# p128fet.net
KiCad netlist of a schematic drawn in EAGLE
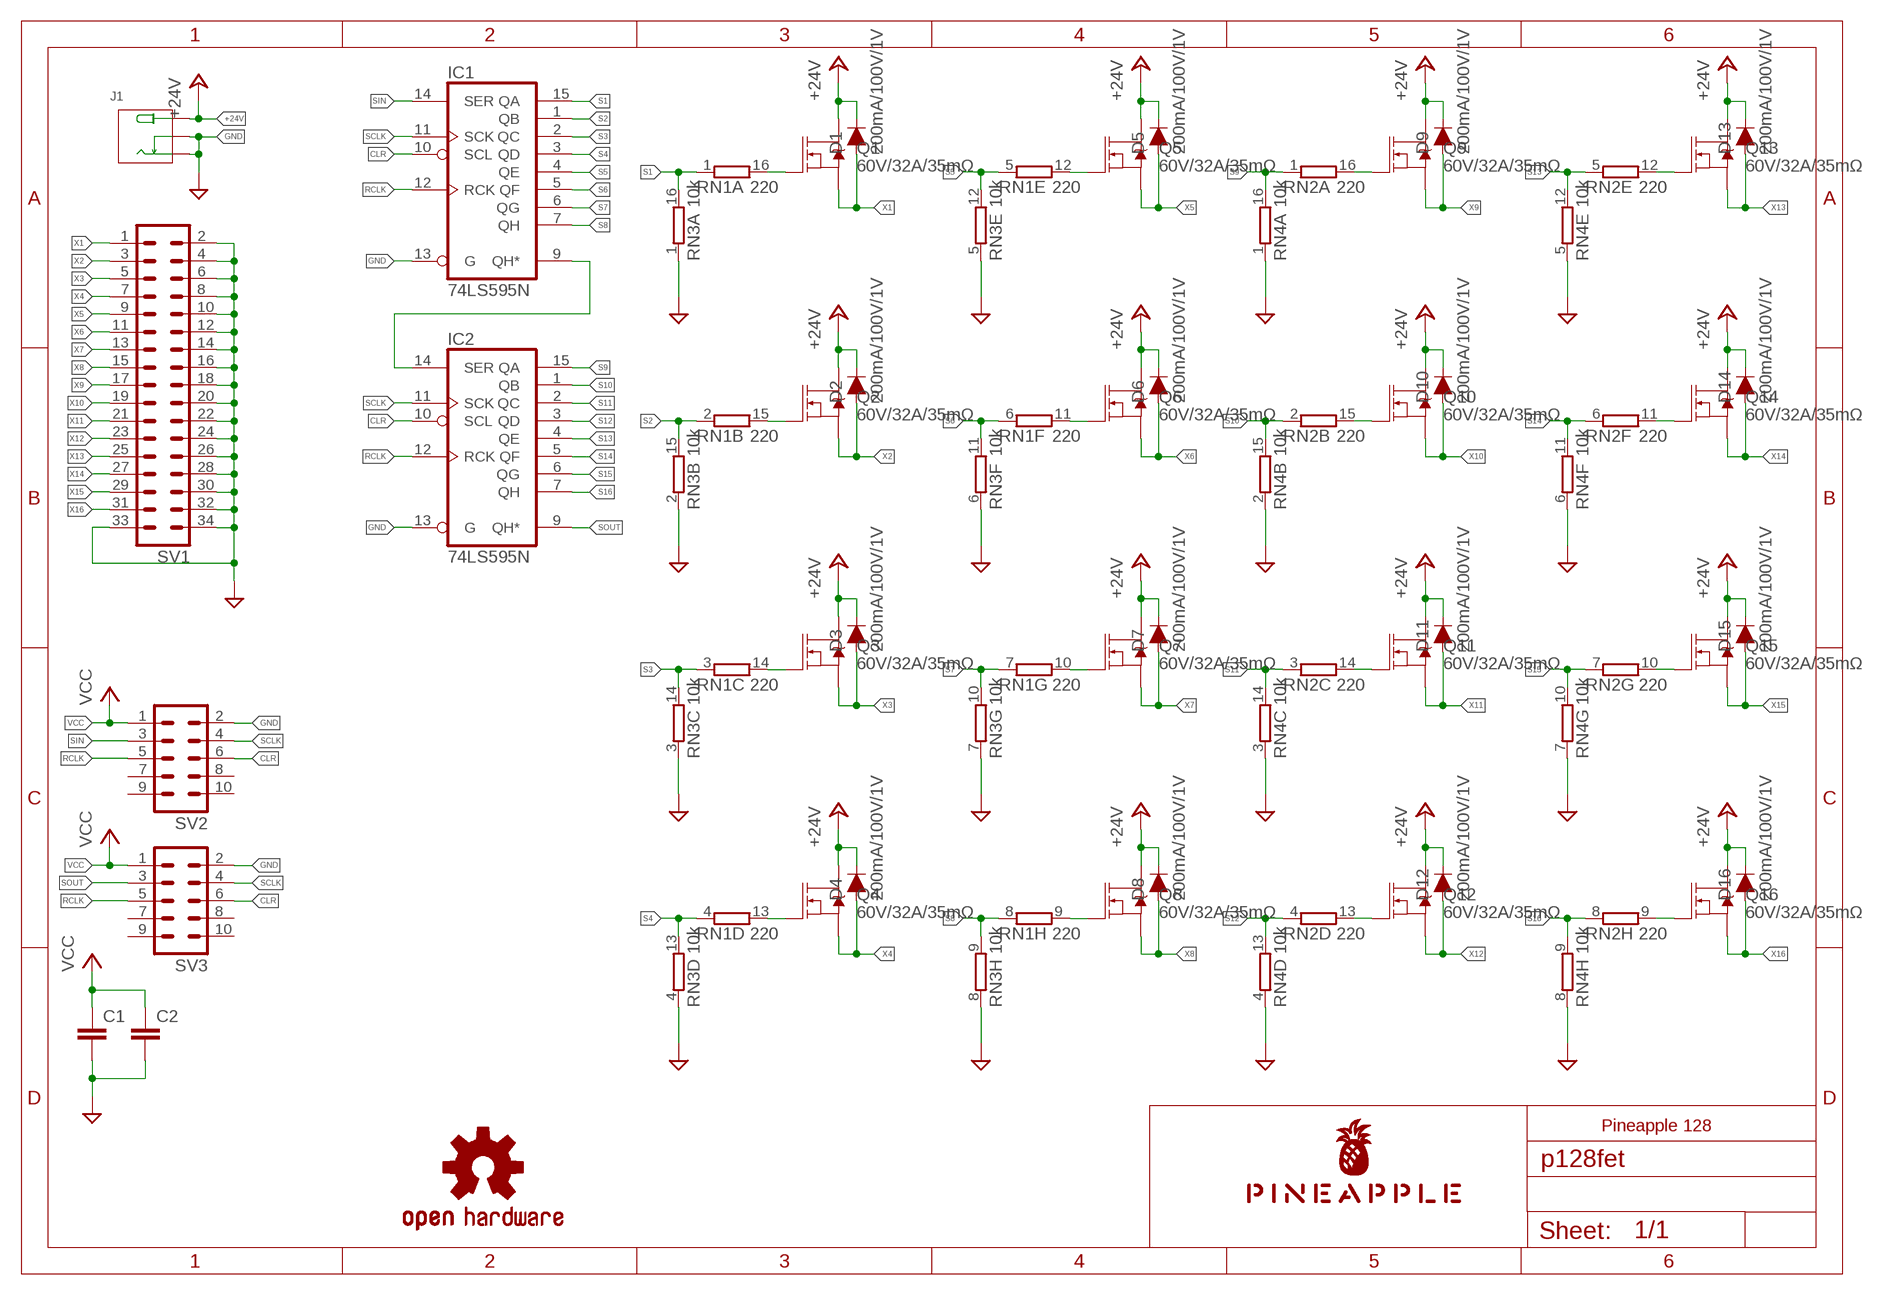
[diagram p0: schematic, sheet 1]

(export (version "E")
  (design (tool "Eeschema 10.0.6"))
  (components
    (comp (ref "C1")
      (value "C-EU025-024X044")
      (footprint "eagle-import:C025-024X044")
      (libsource (lib "eagle-import") (part "C-EU025-024X044"))
    )
    (comp (ref "C2")
      (value "C-EU025-024X044")
      (footprint "eagle-import:C025-024X044")
      (libsource (lib "eagle-import") (part "C-EU025-024X044"))
    )
    (comp (ref "D1")
      (value "200mA/100V/1V")
      (footprint "eagle-import:DIODE-1N4148")
      (libsource (lib "eagle-import") (part "DIODE-1N4148"))
    )
    (comp (ref "D2")
      (value "200mA/100V/1V")
      (footprint "eagle-import:DIODE-1N4148")
      (libsource (lib "eagle-import") (part "DIODE-1N4148"))
    )
    (comp (ref "D3")
      (value "200mA/100V/1V")
      (footprint "eagle-import:DIODE-1N4148")
      (libsource (lib "eagle-import") (part "DIODE-1N4148"))
    )
    (comp (ref "D4")
      (value "200mA/100V/1V")
      (footprint "eagle-import:DIODE-1N4148")
      (libsource (lib "eagle-import") (part "DIODE-1N4148"))
    )
    (comp (ref "D5")
      (value "200mA/100V/1V")
      (footprint "eagle-import:DIODE-1N4148")
      (libsource (lib "eagle-import") (part "DIODE-1N4148"))
    )
    (comp (ref "D6")
      (value "200mA/100V/1V")
      (footprint "eagle-import:DIODE-1N4148")
      (libsource (lib "eagle-import") (part "DIODE-1N4148"))
    )
    (comp (ref "D7")
      (value "200mA/100V/1V")
      (footprint "eagle-import:DIODE-1N4148")
      (libsource (lib "eagle-import") (part "DIODE-1N4148"))
    )
    (comp (ref "D8")
      (value "200mA/100V/1V")
      (footprint "eagle-import:DIODE-1N4148")
      (libsource (lib "eagle-import") (part "DIODE-1N4148"))
    )
    (comp (ref "D9")
      (value "200mA/100V/1V")
      (footprint "eagle-import:DIODE-1N4148")
      (libsource (lib "eagle-import") (part "DIODE-1N4148"))
    )
    (comp (ref "D10")
      (value "200mA/100V/1V")
      (footprint "eagle-import:DIODE-1N4148")
      (libsource (lib "eagle-import") (part "DIODE-1N4148"))
    )
    (comp (ref "D11")
      (value "200mA/100V/1V")
      (footprint "eagle-import:DIODE-1N4148")
      (libsource (lib "eagle-import") (part "DIODE-1N4148"))
    )
    (comp (ref "D12")
      (value "200mA/100V/1V")
      (footprint "eagle-import:DIODE-1N4148")
      (libsource (lib "eagle-import") (part "DIODE-1N4148"))
    )
    (comp (ref "D13")
      (value "200mA/100V/1V")
      (footprint "eagle-import:DIODE-1N4148")
      (libsource (lib "eagle-import") (part "DIODE-1N4148"))
    )
    (comp (ref "D14")
      (value "200mA/100V/1V")
      (footprint "eagle-import:DIODE-1N4148")
      (libsource (lib "eagle-import") (part "DIODE-1N4148"))
    )
    (comp (ref "D15")
      (value "200mA/100V/1V")
      (footprint "eagle-import:DIODE-1N4148")
      (libsource (lib "eagle-import") (part "DIODE-1N4148"))
    )
    (comp (ref "D16")
      (value "200mA/100V/1V")
      (footprint "eagle-import:DIODE-1N4148")
      (libsource (lib "eagle-import") (part "DIODE-1N4148"))
    )
    (comp (ref "IC1")
      (value "74LS595N")
      (footprint "eagle-import:DIL16")
      (libsource (lib "eagle-import") (part "74595NLS"))
    )
    (comp (ref "IC2")
      (value "74LS595N")
      (footprint "eagle-import:DIL16")
      (libsource (lib "eagle-import") (part "74595NLS"))
    )
    (comp (ref "J1")
      (value "JACK-DC-005'DC-005'")
      (footprint "eagle-import:3P-L14.2_W11.0_H9.0MM")
      (libsource (lib "eagle-import") (part "JACK-DC-005'DC-005'"))
    )
    (comp (ref "LOGO1")
      (value "OSHW-LOGOS-COPPER")
      (footprint "eagle-import:OSHW-LOGO-S_COPPER")
      (libsource (lib "eagle-import") (part "OSHW-LOGOS-COPPER"))
    )
    (comp (ref "Q1")
      (value "60V/32A/35mΩ")
      (footprint "eagle-import:TO220V")
      (libsource (lib "eagle-import") (part "MOSFET-NCH-FQP30N06L"))
    )
    (comp (ref "Q2")
      (value "60V/32A/35mΩ")
      (footprint "eagle-import:TO220V")
      (libsource (lib "eagle-import") (part "MOSFET-NCH-FQP30N06L"))
    )
    (comp (ref "Q3")
      (value "60V/32A/35mΩ")
      (footprint "eagle-import:TO220V")
      (libsource (lib "eagle-import") (part "MOSFET-NCH-FQP30N06L"))
    )
    (comp (ref "Q4")
      (value "60V/32A/35mΩ")
      (footprint "eagle-import:TO220V")
      (libsource (lib "eagle-import") (part "MOSFET-NCH-FQP30N06L"))
    )
    (comp (ref "Q5")
      (value "60V/32A/35mΩ")
      (footprint "eagle-import:TO220V")
      (libsource (lib "eagle-import") (part "MOSFET-NCH-FQP30N06L"))
    )
    (comp (ref "Q6")
      (value "60V/32A/35mΩ")
      (footprint "eagle-import:TO220V")
      (libsource (lib "eagle-import") (part "MOSFET-NCH-FQP30N06L"))
    )
    (comp (ref "Q7")
      (value "60V/32A/35mΩ")
      (footprint "eagle-import:TO220V")
      (libsource (lib "eagle-import") (part "MOSFET-NCH-FQP30N06L"))
    )
    (comp (ref "Q8")
      (value "60V/32A/35mΩ")
      (footprint "eagle-import:TO220V")
      (libsource (lib "eagle-import") (part "MOSFET-NCH-FQP30N06L"))
    )
    (comp (ref "Q9")
      (value "60V/32A/35mΩ")
      (footprint "eagle-import:TO220V")
      (libsource (lib "eagle-import") (part "MOSFET-NCH-FQP30N06L"))
    )
    (comp (ref "Q10")
      (value "60V/32A/35mΩ")
      (footprint "eagle-import:TO220V")
      (libsource (lib "eagle-import") (part "MOSFET-NCH-FQP30N06L"))
    )
    (comp (ref "Q11")
      (value "60V/32A/35mΩ")
      (footprint "eagle-import:TO220V")
      (libsource (lib "eagle-import") (part "MOSFET-NCH-FQP30N06L"))
    )
    (comp (ref "Q12")
      (value "60V/32A/35mΩ")
      (footprint "eagle-import:TO220V")
      (libsource (lib "eagle-import") (part "MOSFET-NCH-FQP30N06L"))
    )
    (comp (ref "Q13")
      (value "60V/32A/35mΩ")
      (footprint "eagle-import:TO220V")
      (libsource (lib "eagle-import") (part "MOSFET-NCH-FQP30N06L"))
    )
    (comp (ref "Q14")
      (value "60V/32A/35mΩ")
      (footprint "eagle-import:TO220V")
      (libsource (lib "eagle-import") (part "MOSFET-NCH-FQP30N06L"))
    )
    (comp (ref "Q15")
      (value "60V/32A/35mΩ")
      (footprint "eagle-import:TO220V")
      (libsource (lib "eagle-import") (part "MOSFET-NCH-FQP30N06L"))
    )
    (comp (ref "Q16")
      (value "60V/32A/35mΩ")
      (footprint "eagle-import:TO220V")
      (libsource (lib "eagle-import") (part "MOSFET-NCH-FQP30N06L"))
    )
    (comp (ref "RN1")
      (value "220")
      (footprint "eagle-import:DIL16")
      (libsource (lib "eagle-import") (part "8R-N"))
    )
    (comp (ref "RN2")
      (value "220")
      (footprint "eagle-import:DIL16")
      (libsource (lib "eagle-import") (part "8R-N"))
    )
    (comp (ref "RN3")
      (value "10k")
      (footprint "eagle-import:DIL16")
      (libsource (lib "eagle-import") (part "8R-N"))
    )
    (comp (ref "RN4")
      (value "10k")
      (footprint "eagle-import:DIL16")
      (libsource (lib "eagle-import") (part "8R-N"))
    )
    (comp (ref "SV1")
      (value "ML34L")
      (footprint "eagle-import:ML34L")
      (libsource (lib "eagle-import") (part "ML34L"))
    )
    (comp (ref "SV2")
      (value "ML10L")
      (footprint "eagle-import:ML10L")
      (libsource (lib "eagle-import") (part "ML10L"))
    )
    (comp (ref "SV3")
      (value "ML10L")
      (footprint "eagle-import:ML10L")
      (libsource (lib "eagle-import") (part "ML10L"))
    )
    (comp (ref "U$1")
      (value "PINEAPPLE450_SILK")
      (footprint "eagle-import:PINEAPPLE450_SILK")
      (libsource (lib "eagle-import") (part "PINEAPPLE450_SILK"))
    )
  )
  (nets
    (net (code "1") (name "+24V") (class "Default")
      (node (ref "D1") (pin "C") (pinfunction "C_C") (pintype "passive"))
      (node (ref "D10") (pin "C") (pinfunction "C_C") (pintype "passive"))
      (node (ref "D11") (pin "C") (pinfunction "C_C") (pintype "passive"))
      (node (ref "D12") (pin "C") (pinfunction "C_C") (pintype "passive"))
      (node (ref "D13") (pin "C") (pinfunction "C_C") (pintype "passive"))
      (node (ref "D14") (pin "C") (pinfunction "C_C") (pintype "passive"))
      (node (ref "D15") (pin "C") (pinfunction "C_C") (pintype "passive"))
      (node (ref "D16") (pin "C") (pinfunction "C_C") (pintype "passive"))
      (node (ref "D2") (pin "C") (pinfunction "C_C") (pintype "passive"))
      (node (ref "D3") (pin "C") (pinfunction "C_C") (pintype "passive"))
      (node (ref "D4") (pin "C") (pinfunction "C_C") (pintype "passive"))
      (node (ref "D5") (pin "C") (pinfunction "C_C") (pintype "passive"))
      (node (ref "D6") (pin "C") (pinfunction "C_C") (pintype "passive"))
      (node (ref "D7") (pin "C") (pinfunction "C_C") (pintype "passive"))
      (node (ref "D8") (pin "C") (pinfunction "C_C") (pintype "passive"))
      (node (ref "D9") (pin "C") (pinfunction "C_C") (pintype "passive"))
      (node (ref "J1") (pin "+") (pinfunction "+_+") (pintype "bidirectional"))
      (node (ref "Q1") (pin "2") (pinfunction "D_2") (pintype "bidirectional"))
      (node (ref "Q10") (pin "2") (pinfunction "D_2") (pintype "bidirectional"))
      (node (ref "Q11") (pin "2") (pinfunction "D_2") (pintype "bidirectional"))
      (node (ref "Q12") (pin "2") (pinfunction "D_2") (pintype "bidirectional"))
      (node (ref "Q13") (pin "2") (pinfunction "D_2") (pintype "bidirectional"))
      (node (ref "Q14") (pin "2") (pinfunction "D_2") (pintype "bidirectional"))
      (node (ref "Q15") (pin "2") (pinfunction "D_2") (pintype "bidirectional"))
      (node (ref "Q16") (pin "2") (pinfunction "D_2") (pintype "bidirectional"))
      (node (ref "Q2") (pin "2") (pinfunction "D_2") (pintype "bidirectional"))
      (node (ref "Q3") (pin "2") (pinfunction "D_2") (pintype "bidirectional"))
      (node (ref "Q4") (pin "2") (pinfunction "D_2") (pintype "bidirectional"))
      (node (ref "Q5") (pin "2") (pinfunction "D_2") (pintype "bidirectional"))
      (node (ref "Q6") (pin "2") (pinfunction "D_2") (pintype "bidirectional"))
      (node (ref "Q7") (pin "2") (pinfunction "D_2") (pintype "bidirectional"))
      (node (ref "Q8") (pin "2") (pinfunction "D_2") (pintype "bidirectional"))
      (node (ref "Q9") (pin "2") (pinfunction "D_2") (pintype "bidirectional"))
    )
    (net (code "2") (name "CLR") (class "Default")
      (node (ref "IC1") (pin "10") (pinfunction "SCL_10") (pintype "input"))
      (node (ref "IC2") (pin "10") (pinfunction "SCL_10") (pintype "input"))
      (node (ref "SV2") (pin "6") (pinfunction "6_6") (pintype "passive"))
      (node (ref "SV3") (pin "6") (pinfunction "6_6") (pintype "passive"))
    )
    (net (code "3") (name "GND") (class "Default")
      (node (ref "C1") (pin "2") (pinfunction "2_2") (pintype "passive"))
      (node (ref "C2") (pin "2") (pinfunction "2_2") (pintype "passive"))
      (node (ref "IC1") (pin "13") (pinfunction "G_13") (pintype "input"))
      (node (ref "IC2") (pin "13") (pinfunction "G_13") (pintype "input"))
      (node (ref "J1") (pin "-1") (pinfunction "-_-1") (pintype "bidirectional"))
      (node (ref "J1") (pin "-2") (pinfunction "CDN_-2") (pintype "bidirectional"))
      (node (ref "RN3") (pin "1") (pinfunction "1_1") (pintype "passive"))
      (node (ref "RN3") (pin "2") (pinfunction "1_2") (pintype "passive"))
      (node (ref "RN3") (pin "3") (pinfunction "1_3") (pintype "passive"))
      (node (ref "RN3") (pin "4") (pinfunction "1_4") (pintype "passive"))
      (node (ref "RN3") (pin "5") (pinfunction "1_5") (pintype "passive"))
      (node (ref "RN3") (pin "6") (pinfunction "1_6") (pintype "passive"))
      (node (ref "RN3") (pin "7") (pinfunction "1_7") (pintype "passive"))
      (node (ref "RN3") (pin "8") (pinfunction "1_8") (pintype "passive"))
      (node (ref "RN4") (pin "1") (pinfunction "1_1") (pintype "passive"))
      (node (ref "RN4") (pin "2") (pinfunction "1_2") (pintype "passive"))
      (node (ref "RN4") (pin "3") (pinfunction "1_3") (pintype "passive"))
      (node (ref "RN4") (pin "4") (pinfunction "1_4") (pintype "passive"))
      (node (ref "RN4") (pin "5") (pinfunction "1_5") (pintype "passive"))
      (node (ref "RN4") (pin "6") (pinfunction "1_6") (pintype "passive"))
      (node (ref "RN4") (pin "7") (pinfunction "1_7") (pintype "passive"))
      (node (ref "RN4") (pin "8") (pinfunction "1_8") (pintype "passive"))
      (node (ref "SV1") (pin "10") (pinfunction "10_10") (pintype "passive"))
      (node (ref "SV1") (pin "12") (pinfunction "12_12") (pintype "passive"))
      (node (ref "SV1") (pin "14") (pinfunction "14_14") (pintype "passive"))
      (node (ref "SV1") (pin "16") (pinfunction "16_16") (pintype "passive"))
      (node (ref "SV1") (pin "18") (pinfunction "18_18") (pintype "passive"))
      (node (ref "SV1") (pin "2") (pinfunction "2_2") (pintype "passive"))
      (node (ref "SV1") (pin "20") (pinfunction "20_20") (pintype "passive"))
      (node (ref "SV1") (pin "22") (pinfunction "22_22") (pintype "passive"))
      (node (ref "SV1") (pin "24") (pinfunction "24_24") (pintype "passive"))
      (node (ref "SV1") (pin "26") (pinfunction "26_26") (pintype "passive"))
      (node (ref "SV1") (pin "28") (pinfunction "28_28") (pintype "passive"))
      (node (ref "SV1") (pin "30") (pinfunction "30_30") (pintype "passive"))
      (node (ref "SV1") (pin "32") (pinfunction "32_32") (pintype "passive"))
      (node (ref "SV1") (pin "33") (pinfunction "33_33") (pintype "passive"))
      (node (ref "SV1") (pin "34") (pinfunction "34_34") (pintype "passive"))
      (node (ref "SV1") (pin "4") (pinfunction "4_4") (pintype "passive"))
      (node (ref "SV1") (pin "6") (pinfunction "6_6") (pintype "passive"))
      (node (ref "SV1") (pin "8") (pinfunction "8_8") (pintype "passive"))
      (node (ref "SV2") (pin "2") (pinfunction "2_2") (pintype "passive"))
      (node (ref "SV3") (pin "2") (pinfunction "2_2") (pintype "passive"))
    )
    (net (code "4") (name "Net-(IC1A-QH*)") (class "Default")
      (node (ref "IC1") (pin "9") (pinfunction "QH*_9") (pintype "tri_state"))
      (node (ref "IC2") (pin "14") (pinfunction "SER_14") (pintype "input"))
    )
    (net (code "5") (name "Net-(Q1-G)") (class "Default")
      (node (ref "Q1") (pin "1") (pinfunction "G_1") (pintype "bidirectional"))
      (node (ref "RN1") (pin "16") (pinfunction "2_16") (pintype "passive"))
    )
    (net (code "6") (name "Net-(Q2-G)") (class "Default")
      (node (ref "Q2") (pin "1") (pinfunction "G_1") (pintype "bidirectional"))
      (node (ref "RN1") (pin "15") (pinfunction "2_15") (pintype "passive"))
    )
    (net (code "7") (name "Net-(Q3-G)") (class "Default")
      (node (ref "Q3") (pin "1") (pinfunction "G_1") (pintype "bidirectional"))
      (node (ref "RN1") (pin "14") (pinfunction "2_14") (pintype "passive"))
    )
    (net (code "8") (name "Net-(Q4-G)") (class "Default")
      (node (ref "Q4") (pin "1") (pinfunction "G_1") (pintype "bidirectional"))
      (node (ref "RN1") (pin "13") (pinfunction "2_13") (pintype "passive"))
    )
    (net (code "9") (name "Net-(Q5-G)") (class "Default")
      (node (ref "Q5") (pin "1") (pinfunction "G_1") (pintype "bidirectional"))
      (node (ref "RN1") (pin "12") (pinfunction "2_12") (pintype "passive"))
    )
    (net (code "10") (name "Net-(Q6-G)") (class "Default")
      (node (ref "Q6") (pin "1") (pinfunction "G_1") (pintype "bidirectional"))
      (node (ref "RN1") (pin "11") (pinfunction "2_11") (pintype "passive"))
    )
    (net (code "11") (name "Net-(Q7-G)") (class "Default")
      (node (ref "Q7") (pin "1") (pinfunction "G_1") (pintype "bidirectional"))
      (node (ref "RN1") (pin "10") (pinfunction "2_10") (pintype "passive"))
    )
    (net (code "12") (name "Net-(Q8-G)") (class "Default")
      (node (ref "Q8") (pin "1") (pinfunction "G_1") (pintype "bidirectional"))
      (node (ref "RN1") (pin "9") (pinfunction "2_9") (pintype "passive"))
    )
    (net (code "13") (name "Net-(Q9-G)") (class "Default")
      (node (ref "Q9") (pin "1") (pinfunction "G_1") (pintype "bidirectional"))
      (node (ref "RN2") (pin "16") (pinfunction "2_16") (pintype "passive"))
    )
    (net (code "14") (name "Net-(Q10-G)") (class "Default")
      (node (ref "Q10") (pin "1") (pinfunction "G_1") (pintype "bidirectional"))
      (node (ref "RN2") (pin "15") (pinfunction "2_15") (pintype "passive"))
    )
    (net (code "15") (name "Net-(Q11-G)") (class "Default")
      (node (ref "Q11") (pin "1") (pinfunction "G_1") (pintype "bidirectional"))
      (node (ref "RN2") (pin "14") (pinfunction "2_14") (pintype "passive"))
    )
    (net (code "16") (name "Net-(Q12-G)") (class "Default")
      (node (ref "Q12") (pin "1") (pinfunction "G_1") (pintype "bidirectional"))
      (node (ref "RN2") (pin "13") (pinfunction "2_13") (pintype "passive"))
    )
    (net (code "17") (name "Net-(Q13-G)") (class "Default")
      (node (ref "Q13") (pin "1") (pinfunction "G_1") (pintype "bidirectional"))
      (node (ref "RN2") (pin "12") (pinfunction "2_12") (pintype "passive"))
    )
    (net (code "18") (name "Net-(Q14-G)") (class "Default")
      (node (ref "Q14") (pin "1") (pinfunction "G_1") (pintype "bidirectional"))
      (node (ref "RN2") (pin "11") (pinfunction "2_11") (pintype "passive"))
    )
    (net (code "19") (name "Net-(Q15-G)") (class "Default")
      (node (ref "Q15") (pin "1") (pinfunction "G_1") (pintype "bidirectional"))
      (node (ref "RN2") (pin "10") (pinfunction "2_10") (pintype "passive"))
    )
    (net (code "20") (name "Net-(Q16-G)") (class "Default")
      (node (ref "Q16") (pin "1") (pinfunction "G_1") (pintype "bidirectional"))
      (node (ref "RN2") (pin "9") (pinfunction "2_9") (pintype "passive"))
    )
    (net (code "21") (name "RCLK") (class "Default")
      (node (ref "IC1") (pin "12") (pinfunction "RCK_12") (pintype "input"))
      (node (ref "IC2") (pin "12") (pinfunction "RCK_12") (pintype "input"))
      (node (ref "SV2") (pin "5") (pinfunction "5_5") (pintype "passive"))
      (node (ref "SV3") (pin "5") (pinfunction "5_5") (pintype "passive"))
    )
    (net (code "22") (name "S1") (class "Default")
      (node (ref "IC1") (pin "15") (pinfunction "QA_15") (pintype "tri_state"))
      (node (ref "RN1") (pin "1") (pinfunction "1_1") (pintype "passive"))
      (node (ref "RN3") (pin "16") (pinfunction "2_16") (pintype "passive"))
    )
    (net (code "23") (name "S2") (class "Default")
      (node (ref "IC1") (pin "1") (pinfunction "QB_1") (pintype "tri_state"))
      (node (ref "RN1") (pin "2") (pinfunction "1_2") (pintype "passive"))
      (node (ref "RN3") (pin "15") (pinfunction "2_15") (pintype "passive"))
    )
    (net (code "24") (name "S3") (class "Default")
      (node (ref "IC1") (pin "2") (pinfunction "QC_2") (pintype "tri_state"))
      (node (ref "RN1") (pin "3") (pinfunction "1_3") (pintype "passive"))
      (node (ref "RN3") (pin "14") (pinfunction "2_14") (pintype "passive"))
    )
    (net (code "25") (name "S4") (class "Default")
      (node (ref "IC1") (pin "3") (pinfunction "QD_3") (pintype "tri_state"))
      (node (ref "RN1") (pin "4") (pinfunction "1_4") (pintype "passive"))
      (node (ref "RN3") (pin "13") (pinfunction "2_13") (pintype "passive"))
    )
    (net (code "26") (name "S5") (class "Default")
      (node (ref "IC1") (pin "4") (pinfunction "QE_4") (pintype "tri_state"))
      (node (ref "RN1") (pin "5") (pinfunction "1_5") (pintype "passive"))
      (node (ref "RN3") (pin "12") (pinfunction "2_12") (pintype "passive"))
    )
    (net (code "27") (name "S6") (class "Default")
      (node (ref "IC1") (pin "5") (pinfunction "QF_5") (pintype "tri_state"))
      (node (ref "RN1") (pin "6") (pinfunction "1_6") (pintype "passive"))
      (node (ref "RN3") (pin "11") (pinfunction "2_11") (pintype "passive"))
    )
    (net (code "28") (name "S7") (class "Default")
      (node (ref "IC1") (pin "6") (pinfunction "QG_6") (pintype "tri_state"))
      (node (ref "RN1") (pin "7") (pinfunction "1_7") (pintype "passive"))
      (node (ref "RN3") (pin "10") (pinfunction "2_10") (pintype "passive"))
    )
    (net (code "29") (name "S8") (class "Default")
      (node (ref "IC1") (pin "7") (pinfunction "QH_7") (pintype "tri_state"))
      (node (ref "RN1") (pin "8") (pinfunction "1_8") (pintype "passive"))
      (node (ref "RN3") (pin "9") (pinfunction "2_9") (pintype "passive"))
    )
    (net (code "30") (name "S9") (class "Default")
      (node (ref "IC2") (pin "15") (pinfunction "QA_15") (pintype "tri_state"))
      (node (ref "RN2") (pin "1") (pinfunction "1_1") (pintype "passive"))
      (node (ref "RN4") (pin "16") (pinfunction "2_16") (pintype "passive"))
    )
    (net (code "31") (name "S10") (class "Default")
      (node (ref "IC2") (pin "1") (pinfunction "QB_1") (pintype "tri_state"))
      (node (ref "RN2") (pin "2") (pinfunction "1_2") (pintype "passive"))
      (node (ref "RN4") (pin "15") (pinfunction "2_15") (pintype "passive"))
    )
    (net (code "32") (name "S11") (class "Default")
      (node (ref "IC2") (pin "2") (pinfunction "QC_2") (pintype "tri_state"))
      (node (ref "RN2") (pin "3") (pinfunction "1_3") (pintype "passive"))
      (node (ref "RN4") (pin "14") (pinfunction "2_14") (pintype "passive"))
    )
    (net (code "33") (name "S12") (class "Default")
      (node (ref "IC2") (pin "3") (pinfunction "QD_3") (pintype "tri_state"))
      (node (ref "RN2") (pin "4") (pinfunction "1_4") (pintype "passive"))
      (node (ref "RN4") (pin "13") (pinfunction "2_13") (pintype "passive"))
    )
    (net (code "34") (name "S13") (class "Default")
      (node (ref "IC2") (pin "4") (pinfunction "QE_4") (pintype "tri_state"))
      (node (ref "RN2") (pin "5") (pinfunction "1_5") (pintype "passive"))
      (node (ref "RN4") (pin "12") (pinfunction "2_12") (pintype "passive"))
    )
    (net (code "35") (name "S14") (class "Default")
      (node (ref "IC2") (pin "5") (pinfunction "QF_5") (pintype "tri_state"))
      (node (ref "RN2") (pin "6") (pinfunction "1_6") (pintype "passive"))
      (node (ref "RN4") (pin "11") (pinfunction "2_11") (pintype "passive"))
    )
    (net (code "36") (name "S15") (class "Default")
      (node (ref "IC2") (pin "6") (pinfunction "QG_6") (pintype "tri_state"))
      (node (ref "RN2") (pin "7") (pinfunction "1_7") (pintype "passive"))
      (node (ref "RN4") (pin "10") (pinfunction "2_10") (pintype "passive"))
    )
    (net (code "37") (name "S16") (class "Default")
      (node (ref "IC2") (pin "7") (pinfunction "QH_7") (pintype "tri_state"))
      (node (ref "RN2") (pin "8") (pinfunction "1_8") (pintype "passive"))
      (node (ref "RN4") (pin "9") (pinfunction "2_9") (pintype "passive"))
    )
    (net (code "38") (name "SCLK") (class "Default")
      (node (ref "IC1") (pin "11") (pinfunction "SCK_11") (pintype "input"))
      (node (ref "IC2") (pin "11") (pinfunction "SCK_11") (pintype "input"))
      (node (ref "SV2") (pin "4") (pinfunction "4_4") (pintype "passive"))
      (node (ref "SV3") (pin "4") (pinfunction "4_4") (pintype "passive"))
    )
    (net (code "39") (name "SIN") (class "Default")
      (node (ref "IC1") (pin "14") (pinfunction "SER_14") (pintype "input"))
      (node (ref "SV2") (pin "3") (pinfunction "3_3") (pintype "passive"))
    )
    (net (code "40") (name "SOUT") (class "Default")
      (node (ref "IC2") (pin "9") (pinfunction "QH*_9") (pintype "tri_state"))
      (node (ref "SV3") (pin "3") (pinfunction "3_3") (pintype "passive"))
    )
    (net (code "41") (name "VCC") (class "Default")
      (node (ref "C1") (pin "1") (pinfunction "1_1") (pintype "passive"))
      (node (ref "C2") (pin "1") (pinfunction "1_1") (pintype "passive"))
      (node (ref "SV2") (pin "1") (pinfunction "1_1") (pintype "passive"))
      (node (ref "SV3") (pin "1") (pinfunction "1_1") (pintype "passive"))
    )
    (net (code "42") (name "X1") (class "Default")
      (node (ref "D1") (pin "A") (pinfunction "A_A") (pintype "passive"))
      (node (ref "Q1") (pin "3") (pinfunction "S_3") (pintype "bidirectional"))
      (node (ref "SV1") (pin "1") (pinfunction "1_1") (pintype "passive"))
    )
    (net (code "43") (name "X2") (class "Default")
      (node (ref "D2") (pin "A") (pinfunction "A_A") (pintype "passive"))
      (node (ref "Q2") (pin "3") (pinfunction "S_3") (pintype "bidirectional"))
      (node (ref "SV1") (pin "3") (pinfunction "3_3") (pintype "passive"))
    )
    (net (code "44") (name "X3") (class "Default")
      (node (ref "D3") (pin "A") (pinfunction "A_A") (pintype "passive"))
      (node (ref "Q3") (pin "3") (pinfunction "S_3") (pintype "bidirectional"))
      (node (ref "SV1") (pin "5") (pinfunction "5_5") (pintype "passive"))
    )
    (net (code "45") (name "X4") (class "Default")
      (node (ref "D4") (pin "A") (pinfunction "A_A") (pintype "passive"))
      (node (ref "Q4") (pin "3") (pinfunction "S_3") (pintype "bidirectional"))
      (node (ref "SV1") (pin "7") (pinfunction "7_7") (pintype "passive"))
    )
    (net (code "46") (name "X5") (class "Default")
      (node (ref "D5") (pin "A") (pinfunction "A_A") (pintype "passive"))
      (node (ref "Q5") (pin "3") (pinfunction "S_3") (pintype "bidirectional"))
      (node (ref "SV1") (pin "9") (pinfunction "9_9") (pintype "passive"))
    )
    (net (code "47") (name "X6") (class "Default")
      (node (ref "D6") (pin "A") (pinfunction "A_A") (pintype "passive"))
      (node (ref "Q6") (pin "3") (pinfunction "S_3") (pintype "bidirectional"))
      (node (ref "SV1") (pin "11") (pinfunction "11_11") (pintype "passive"))
    )
    (net (code "48") (name "X7") (class "Default")
      (node (ref "D7") (pin "A") (pinfunction "A_A") (pintype "passive"))
      (node (ref "Q7") (pin "3") (pinfunction "S_3") (pintype "bidirectional"))
      (node (ref "SV1") (pin "13") (pinfunction "13_13") (pintype "passive"))
    )
    (net (code "49") (name "X8") (class "Default")
      (node (ref "D8") (pin "A") (pinfunction "A_A") (pintype "passive"))
      (node (ref "Q8") (pin "3") (pinfunction "S_3") (pintype "bidirectional"))
      (node (ref "SV1") (pin "15") (pinfunction "15_15") (pintype "passive"))
    )
    (net (code "50") (name "X9") (class "Default")
      (node (ref "D9") (pin "A") (pinfunction "A_A") (pintype "passive"))
      (node (ref "Q9") (pin "3") (pinfunction "S_3") (pintype "bidirectional"))
      (node (ref "SV1") (pin "17") (pinfunction "17_17") (pintype "passive"))
    )
    (net (code "51") (name "X10") (class "Default")
      (node (ref "D10") (pin "A") (pinfunction "A_A") (pintype "passive"))
      (node (ref "Q10") (pin "3") (pinfunction "S_3") (pintype "bidirectional"))
      (node (ref "SV1") (pin "19") (pinfunction "19_19") (pintype "passive"))
    )
    (net (code "52") (name "X11") (class "Default")
      (node (ref "D11") (pin "A") (pinfunction "A_A") (pintype "passive"))
      (node (ref "Q11") (pin "3") (pinfunction "S_3") (pintype "bidirectional"))
      (node (ref "SV1") (pin "21") (pinfunction "21_21") (pintype "passive"))
    )
    (net (code "53") (name "X12") (class "Default")
      (node (ref "D12") (pin "A") (pinfunction "A_A") (pintype "passive"))
      (node (ref "Q12") (pin "3") (pinfunction "S_3") (pintype "bidirectional"))
      (node (ref "SV1") (pin "23") (pinfunction "23_23") (pintype "passive"))
    )
    (net (code "54") (name "X13") (class "Default")
      (node (ref "D13") (pin "A") (pinfunction "A_A") (pintype "passive"))
      (node (ref "Q13") (pin "3") (pinfunction "S_3") (pintype "bidirectional"))
      (node (ref "SV1") (pin "25") (pinfunction "25_25") (pintype "passive"))
    )
    (net (code "55") (name "X14") (class "Default")
      (node (ref "D14") (pin "A") (pinfunction "A_A") (pintype "passive"))
      (node (ref "Q14") (pin "3") (pinfunction "S_3") (pintype "bidirectional"))
      (node (ref "SV1") (pin "27") (pinfunction "27_27") (pintype "passive"))
    )
    (net (code "56") (name "X15") (class "Default")
      (node (ref "D15") (pin "A") (pinfunction "A_A") (pintype "passive"))
      (node (ref "Q15") (pin "3") (pinfunction "S_3") (pintype "bidirectional"))
      (node (ref "SV1") (pin "29") (pinfunction "29_29") (pintype "passive"))
    )
    (net (code "57") (name "X16") (class "Default")
      (node (ref "D16") (pin "A") (pinfunction "A_A") (pintype "passive"))
      (node (ref "Q16") (pin "3") (pinfunction "S_3") (pintype "bidirectional"))
      (node (ref "SV1") (pin "31") (pinfunction "31_31") (pintype "passive"))
    )
    (net (code "58") (name "unconnected-(SV2-Pad7)") (class "Default")
      (node (ref "SV2") (pin "7") (pinfunction "7_7") (pintype "passive"))
    )
    (net (code "59") (name "unconnected-(SV2-Pad8)") (class "Default")
      (node (ref "SV2") (pin "8") (pinfunction "8_8") (pintype "passive"))
    )
    (net (code "60") (name "unconnected-(SV2-Pad9)") (class "Default")
      (node (ref "SV2") (pin "9") (pinfunction "9_9") (pintype "passive"))
    )
    (net (code "61") (name "unconnected-(SV2-Pad10)") (class "Default")
      (node (ref "SV2") (pin "10") (pinfunction "10_10") (pintype "passive"))
    )
    (net (code "62") (name "unconnected-(SV3-Pad7)") (class "Default")
      (node (ref "SV3") (pin "7") (pinfunction "7_7") (pintype "passive"))
    )
    (net (code "63") (name "unconnected-(SV3-Pad8)") (class "Default")
      (node (ref "SV3") (pin "8") (pinfunction "8_8") (pintype "passive"))
    )
    (net (code "64") (name "unconnected-(SV3-Pad9)") (class "Default")
      (node (ref "SV3") (pin "9") (pinfunction "9_9") (pintype "passive"))
    )
    (net (code "65") (name "unconnected-(SV3-Pad10)") (class "Default")
      (node (ref "SV3") (pin "10") (pinfunction "10_10") (pintype "passive"))
    )
  )
)
